# 9DOF-Razor-v22.net
KiCad netlist of a schematic drawn in EAGLE
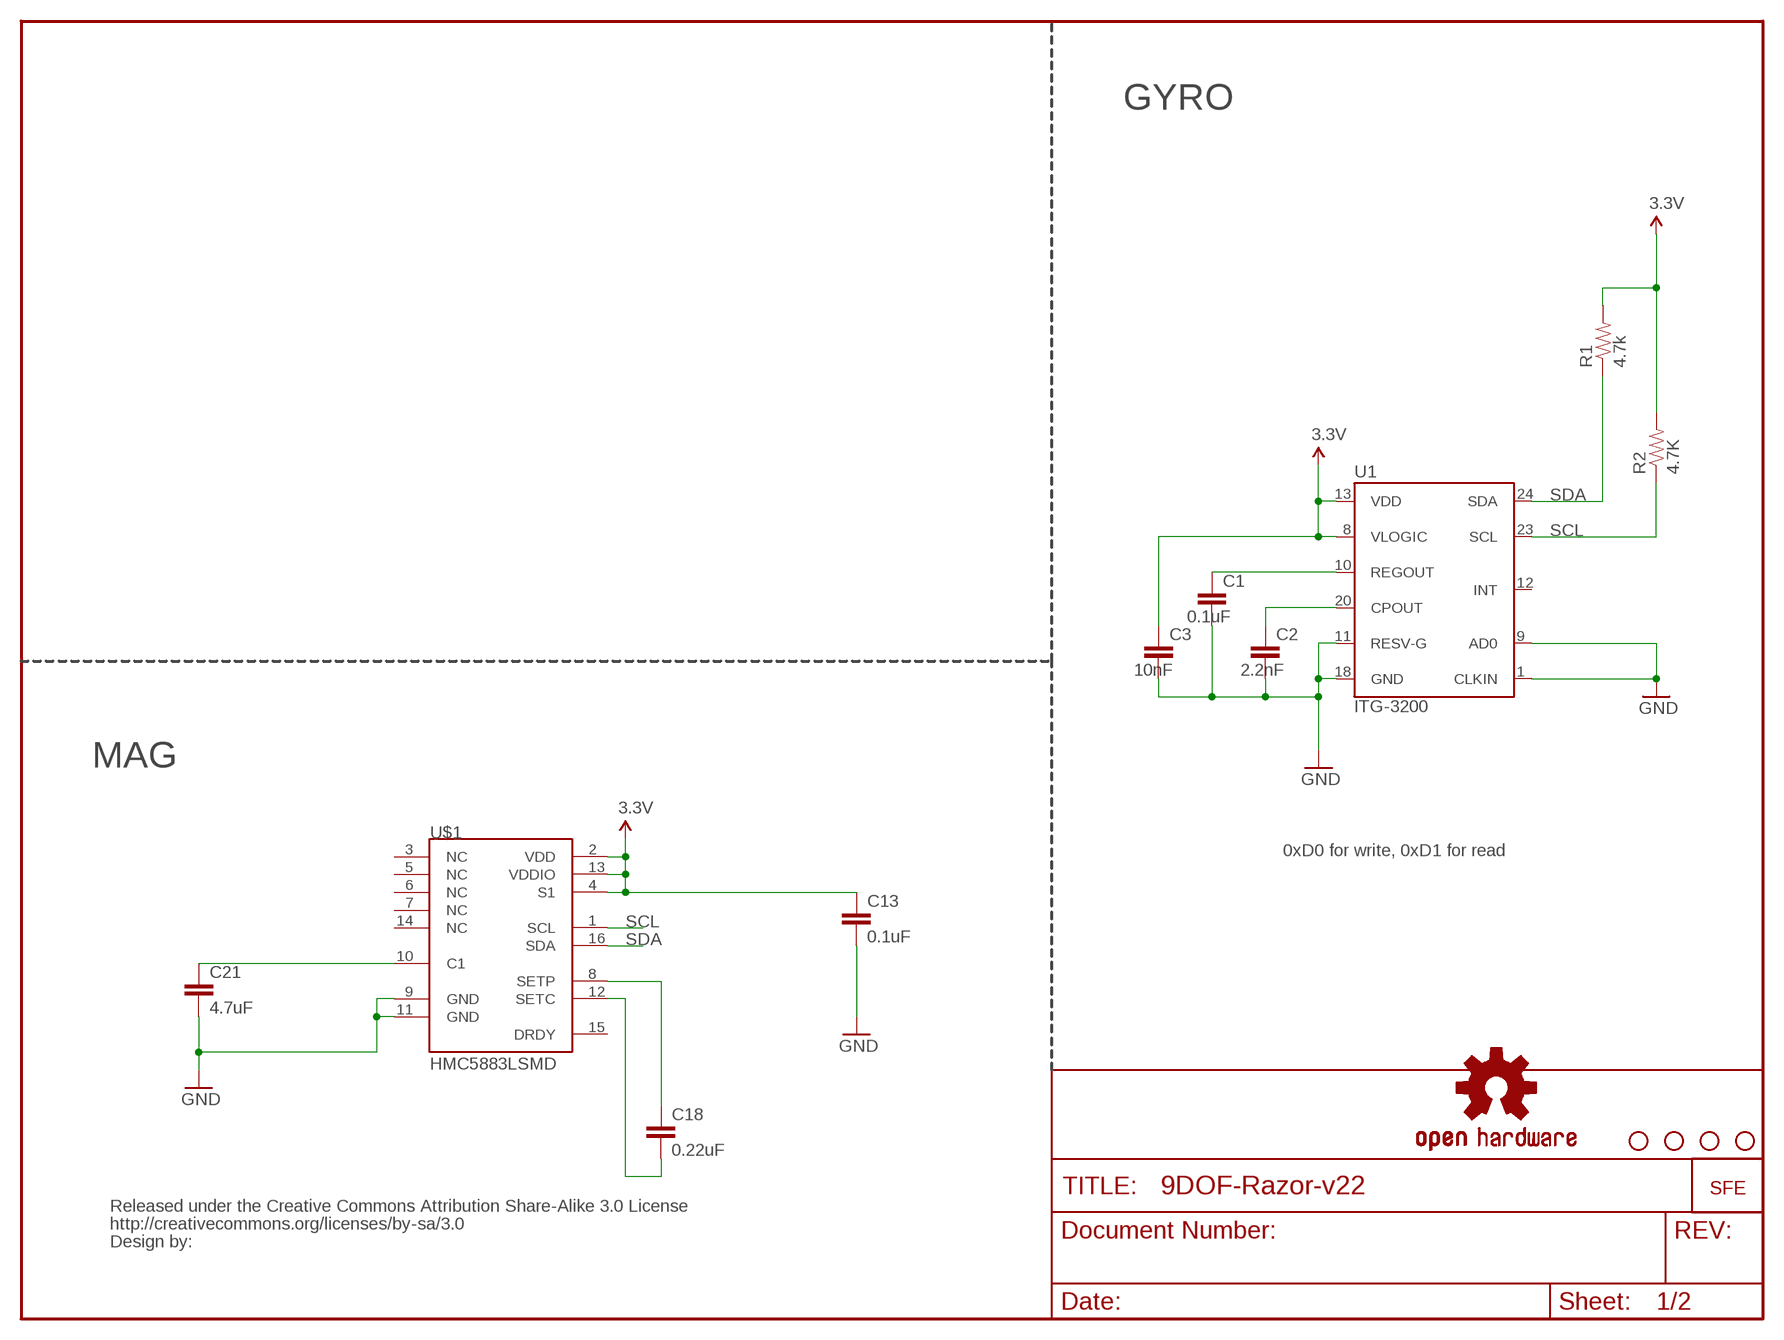
[diagram p0: schematic, sheet 1]
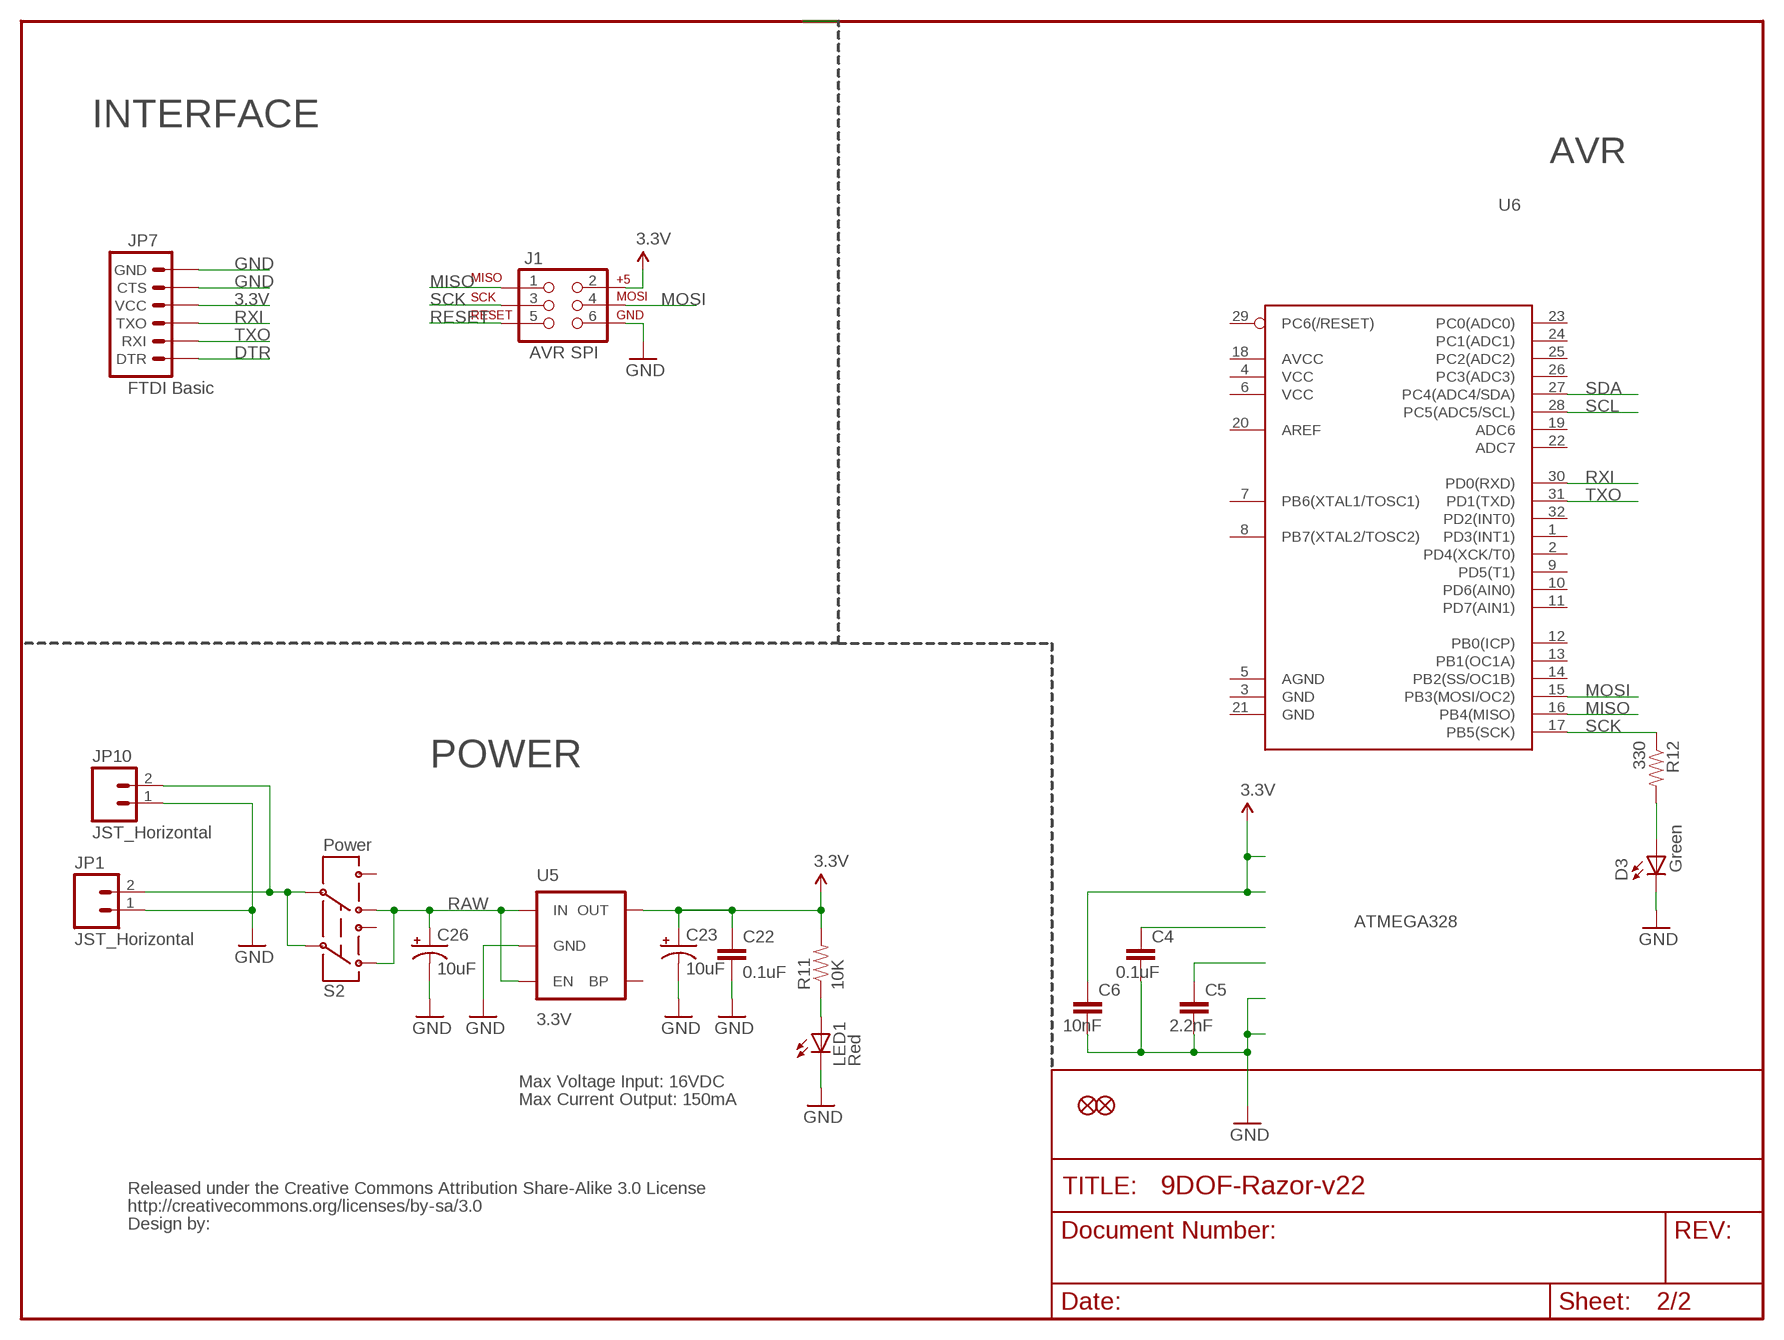
[diagram p1: schematic, sheet 2]

(export (version "E")
  (design (tool "Eeschema 10.0.6"))
  (components
    (comp (ref "C1")
      (value "0.1uF")
      (footprint "eagle-import:0402-CAP")
      (libsource (lib "eagle-import") (part "CAP0402-CAP"))
    )
    (comp (ref "C2")
      (value "2.2nF")
      (footprint "eagle-import:0402-CAP")
      (libsource (lib "eagle-import") (part "CAP0402-CAP"))
    )
    (comp (ref "C3")
      (value "10nF")
      (footprint "eagle-import:0402-CAP")
      (libsource (lib "eagle-import") (part "CAP0402-CAP"))
    )
    (comp (ref "C13")
      (value "0.1uF")
      (footprint "eagle-import:0402-CAP")
      (libsource (lib "eagle-import") (part "CAP0402-CAP"))
    )
    (comp (ref "C18")
      (value "0.22uF")
      (footprint "eagle-import:0402-CAP")
      (libsource (lib "eagle-import") (part "CAP0402-CAP"))
    )
    (comp (ref "C21")
      (value "4.7uF")
      (footprint "eagle-import:0402-CAP")
      (libsource (lib "eagle-import") (part "CAP0402-CAP"))
    )
    (comp (ref "JP2")
      (value "STAND-OFF")
      (footprint "eagle-import:STAND-OFF")
      (libsource (lib "eagle-import") (part "STAND-OFF"))
    )
    (comp (ref "JP3")
      (value "LOGO-SFENEW")
      (footprint "eagle-import:SFE-NEW-WEBLOGO")
      (libsource (lib "eagle-import") (part "LOGO-SFENEW"))
    )
    (comp (ref "JP4")
      (value "STAND-OFF")
      (footprint "eagle-import:STAND-OFF")
      (libsource (lib "eagle-import") (part "STAND-OFF"))
    )
    (comp (ref "JP5")
      (value "STAND-OFF")
      (footprint "eagle-import:STAND-OFF")
      (libsource (lib "eagle-import") (part "STAND-OFF"))
    )
    (comp (ref "JP6")
      (value "STAND-OFF")
      (footprint "eagle-import:STAND-OFF")
      (libsource (lib "eagle-import") (part "STAND-OFF"))
    )
    (comp (ref "R1")
      (value "4.7k")
      (footprint "eagle-import:0402-RES")
      (libsource (lib "eagle-import") (part "RESISTOR0402-RES"))
    )
    (comp (ref "R2")
      (value "4.7K")
      (footprint "eagle-import:0402-RES")
      (libsource (lib "eagle-import") (part "RESISTOR0402-RES"))
    )
    (comp (ref "U$1")
      (value "HMC5883LSMD")
      (footprint "eagle-import:16LPCC")
      (libsource (lib "eagle-import") (part "HMC5883LSMD"))
    )
    (comp (ref "U$2")
      (value "CREATIVE_COMMONS")
      (footprint "eagle-import:CREATIVE_COMMONS")
      (libsource (lib "eagle-import") (part "CREATIVE_COMMONS"))
    )
    (comp (ref "U$4")
      (value "OSHW-LOGOL")
      (footprint "eagle-import:OSHW-LOGO-L")
      (libsource (lib "eagle-import") (part "OSHW-LOGOL"))
    )
    (comp (ref "U1")
      (value "ITG-3200")
      (footprint "eagle-import:QFN-24")
      (libsource (lib "eagle-import") (part "ITG-3200"))
    )
    (comp (ref "C4")
      (value "0.1uF")
      (footprint "eagle-import:0402-CAP")
      (libsource (lib "eagle-import") (part "CAP0402-CAP"))
    )
    (comp (ref "C5")
      (value "2.2nF")
      (footprint "eagle-import:0402-CAP")
      (libsource (lib "eagle-import") (part "CAP0402-CAP"))
    )
    (comp (ref "C6")
      (value "10nF")
      (footprint "eagle-import:0402-CAP")
      (libsource (lib "eagle-import") (part "CAP0402-CAP"))
    )
    (comp (ref "C22")
      (value "0.1uF")
      (footprint "eagle-import:0402-CAP")
      (libsource (lib "eagle-import") (part "CAP0402-CAP"))
    )
    (comp (ref "C23")
      (value "10uF")
      (footprint "eagle-import:EIA3216")
      (libsource (lib "eagle-import") (part "CAP_POL1206"))
    )
    (comp (ref "C26")
      (value "10uF")
      (footprint "eagle-import:EIA3216")
      (libsource (lib "eagle-import") (part "CAP_POL1206"))
    )
    (comp (ref "D3")
      (value "Green")
      (footprint "eagle-import:LED-0603")
      (libsource (lib "eagle-import") (part "LED0603"))
    )
    (comp (ref "J1")
      (value "AVR_SPI_PRG_6PTH")
      (footprint "eagle-import:2X3")
      (libsource (lib "eagle-import") (part "AVR_SPI_PRG_6PTH"))
    )
    (comp (ref "JP1")
      (value "JST_Horizontal")
      (footprint "eagle-import:JST-2-SMD")
      (libsource (lib "eagle-import") (part "M02-JST-2MM-SMT"))
    )
    (comp (ref "JP7")
      (value "FTDI Basic")
      (footprint "eagle-import:1X06")
      (libsource (lib "eagle-import") (part "ARDUINO_SERIAL_PROGRAMPTH"))
    )
    (comp (ref "JP10")
      (value "JST_Horizontal")
      (footprint "eagle-import:1X02")
      (libsource (lib "eagle-import") (part "M02PTH"))
    )
    (comp (ref "JP11")
      (value "FIDUCIAL1X2.5")
      (footprint "eagle-import:FIDUCIAL-1X2.5")
      (libsource (lib "eagle-import") (part "FIDUCIAL1X2.5"))
    )
    (comp (ref "JP12")
      (value "FIDUCIAL1X2.5")
      (footprint "eagle-import:FIDUCIAL-1X2.5")
      (libsource (lib "eagle-import") (part "FIDUCIAL1X2.5"))
    )
    (comp (ref "LED1")
      (value "Red")
      (footprint "eagle-import:LED-0603")
      (libsource (lib "eagle-import") (part "LED0603"))
    )
    (comp (ref "R11")
      (value "10K")
      (footprint "eagle-import:0402-RES")
      (libsource (lib "eagle-import") (part "RESISTOR0402-RES"))
    )
    (comp (ref "R12")
      (value "330")
      (footprint "eagle-import:0402-RES")
      (libsource (lib "eagle-import") (part "RESISTOR0402-RES"))
    )
    (comp (ref "S2")
      (value "Power")
      (footprint "eagle-import:AYZ0202")
      (libsource (lib "eagle-import") (part "SWITCH-DPDTSMD"))
    )
    (comp (ref "U$3")
      (value "CREATIVE_COMMONS")
      (footprint "eagle-import:CREATIVE_COMMONS")
      (libsource (lib "eagle-import") (part "CREATIVE_COMMONS"))
    )
    (comp (ref "U5")
      (value "3.3V")
      (footprint "eagle-import:SOT23-5")
      (libsource (lib "eagle-import") (part "V_REG_LDOSMD"))
    )
    (comp (ref "U6")
      (value "ATMEGA328")
      (footprint "eagle-import:TQFP32-08")
      (libsource (lib "eagle-import") (part "ATMEGA168"))
    )
  )
  (nets
    (net (code "1") (name "3.3V") (class "Default")
      (node (ref "C13") (pin "1") (pinfunction "1_1") (pintype "passive"))
      (node (ref "C22") (pin "1") (pinfunction "1_1") (pintype "passive"))
      (node (ref "C23") (pin "A") (pinfunction "+_A") (pintype "passive"))
      (node (ref "C3") (pin "1") (pinfunction "1_1") (pintype "passive"))
      (node (ref "C6") (pin "1") (pinfunction "1_1") (pintype "passive"))
      (node (ref "J1") (pin "2") (pinfunction "2_2") (pintype "passive"))
      (node (ref "JP7") (pin "4") (pinfunction "VCC_4") (pintype "passive"))
      (node (ref "R1") (pin "2") (pinfunction "2_2") (pintype "passive"))
      (node (ref "R11") (pin "2") (pinfunction "2_2") (pintype "passive"))
      (node (ref "R2") (pin "2") (pinfunction "2_2") (pintype "passive"))
      (node (ref "U$1") (pin "13") (pinfunction "VDDIO_13") (pintype "bidirectional"))
      (node (ref "U$1") (pin "2") (pinfunction "VDD_2") (pintype "bidirectional"))
      (node (ref "U$1") (pin "4") (pinfunction "S1_4") (pintype "bidirectional"))
      (node (ref "U1") (pin "13") (pinfunction "VDD_13") (pintype "bidirectional"))
      (node (ref "U1") (pin "8") (pinfunction "VLOGIC_8") (pintype "bidirectional"))
      (node (ref "U5") (pin "5") (pinfunction "OUT_5") (pintype "passive"))
    )
    (net (code "2") (name "DTR") (class "Default")
      (node (ref "JP7") (pin "1") (pinfunction "DTR_1") (pintype "passive"))
    )
    (net (code "3") (name "GND") (class "Default")
      (node (ref "C1") (pin "2") (pinfunction "2_2") (pintype "passive"))
      (node (ref "C13") (pin "2") (pinfunction "2_2") (pintype "passive"))
      (node (ref "C2") (pin "2") (pinfunction "2_2") (pintype "passive"))
      (node (ref "C21") (pin "2") (pinfunction "2_2") (pintype "passive"))
      (node (ref "C22") (pin "2") (pinfunction "2_2") (pintype "passive"))
      (node (ref "C23") (pin "C") (pinfunction "-_C") (pintype "passive"))
      (node (ref "C26") (pin "C") (pinfunction "-_C") (pintype "passive"))
      (node (ref "C3") (pin "2") (pinfunction "2_2") (pintype "passive"))
      (node (ref "C4") (pin "2") (pinfunction "2_2") (pintype "passive"))
      (node (ref "C5") (pin "2") (pinfunction "2_2") (pintype "passive"))
      (node (ref "C6") (pin "2") (pinfunction "2_2") (pintype "passive"))
      (node (ref "D3") (pin "C") (pinfunction "C_C") (pintype "passive"))
      (node (ref "J1") (pin "6") (pinfunction "6_6") (pintype "passive"))
      (node (ref "JP1") (pin "1") (pinfunction "1_1") (pintype "passive"))
      (node (ref "JP10") (pin "1") (pinfunction "1_1") (pintype "passive"))
      (node (ref "JP7") (pin "5") (pinfunction "CTS_5") (pintype "passive"))
      (node (ref "JP7") (pin "6") (pinfunction "GND_6") (pintype "passive"))
      (node (ref "LED1") (pin "C") (pinfunction "C_C") (pintype "passive"))
      (node (ref "U$1") (pin "11") (pinfunction "GND_11") (pintype "bidirectional"))
      (node (ref "U$1") (pin "9") (pinfunction "GND_9") (pintype "bidirectional"))
      (node (ref "U1") (pin "1") (pinfunction "CLKIN_1") (pintype "bidirectional"))
      (node (ref "U1") (pin "11") (pinfunction "RESV-G_11") (pintype "bidirectional"))
      (node (ref "U1") (pin "18") (pinfunction "GND_18") (pintype "bidirectional"))
      (node (ref "U1") (pin "9") (pinfunction "AD0_9") (pintype "bidirectional"))
      (node (ref "U5") (pin "2") (pinfunction "GND_2") (pintype "input"))
    )
    (net (code "4") (name "MISO") (class "Default")
      (node (ref "J1") (pin "1") (pinfunction "1_1") (pintype "passive"))
      (node (ref "U6") (pin "16") (pinfunction "PB4(MISO)_16") (pintype "bidirectional"))
    )
    (net (code "5") (name "MOSI") (class "Default")
      (node (ref "J1") (pin "4") (pinfunction "4_4") (pintype "passive"))
      (node (ref "U6") (pin "15") (pinfunction "PB3(MOSI/OC2)_15") (pintype "bidirectional"))
    )
    (net (code "6") (name "Net-(D3-PadA)") (class "Default")
      (node (ref "D3") (pin "A") (pinfunction "A_A") (pintype "passive"))
      (node (ref "R12") (pin "2") (pinfunction "2_2") (pintype "passive"))
    )
    (net (code "7") (name "Net-(JP1-Pad2)") (class "Default")
      (node (ref "JP1") (pin "2") (pinfunction "2_2") (pintype "passive"))
      (node (ref "JP10") (pin "2") (pinfunction "2_2") (pintype "passive"))
      (node (ref "S2") (pin "2") (pinfunction "2_2") (pintype "bidirectional"))
      (node (ref "S2") (pin "5") (pinfunction "5_5") (pintype "bidirectional"))
    )
    (net (code "8") (name "Net-(LED1-PadA)") (class "Default")
      (node (ref "LED1") (pin "A") (pinfunction "A_A") (pintype "passive"))
      (node (ref "R11") (pin "1") (pinfunction "1_1") (pintype "passive"))
    )
    (net (code "9") (name "Net-(U$1-C1)") (class "Default")
      (node (ref "C21") (pin "1") (pinfunction "1_1") (pintype "passive"))
      (node (ref "U$1") (pin "10") (pinfunction "C1_10") (pintype "bidirectional"))
    )
    (net (code "10") (name "Net-(U$1-SETC)") (class "Default")
      (node (ref "C18") (pin "1") (pinfunction "1_1") (pintype "passive"))
      (node (ref "U$1") (pin "12") (pinfunction "SETC_12") (pintype "bidirectional"))
    )
    (net (code "11") (name "Net-(U$1-SETP)") (class "Default")
      (node (ref "C18") (pin "2") (pinfunction "2_2") (pintype "passive"))
      (node (ref "U$1") (pin "8") (pinfunction "SETP_8") (pintype "bidirectional"))
    )
    (net (code "12") (name "Net-(U1-CPOUT)") (class "Default")
      (node (ref "C2") (pin "1") (pinfunction "1_1") (pintype "passive"))
      (node (ref "U1") (pin "20") (pinfunction "CPOUT_20") (pintype "bidirectional"))
    )
    (net (code "13") (name "Net-(U1-REGOUT)") (class "Default")
      (node (ref "C1") (pin "1") (pinfunction "1_1") (pintype "passive"))
      (node (ref "U1") (pin "10") (pinfunction "REGOUT_10") (pintype "bidirectional"))
    )
    (net (code "14") (name "RAW") (class "Default")
      (node (ref "C26") (pin "A") (pinfunction "+_A") (pintype "passive"))
      (node (ref "S2") (pin "1") (pinfunction "1_1") (pintype "bidirectional"))
      (node (ref "S2") (pin "4") (pinfunction "4_4") (pintype "bidirectional"))
      (node (ref "U5") (pin "1") (pinfunction "IN_1") (pintype "input"))
      (node (ref "U5") (pin "3") (pinfunction "EN_3") (pintype "input"))
    )
    (net (code "15") (name "RESET") (class "Default")
      (node (ref "J1") (pin "5") (pinfunction "5_5") (pintype "passive"))
    )
    (net (code "16") (name "RXI") (class "Default")
      (node (ref "JP7") (pin "3") (pinfunction "TXO_3") (pintype "passive"))
      (node (ref "U6") (pin "30") (pinfunction "PD0(RXD)_30") (pintype "bidirectional"))
    )
    (net (code "17") (name "SCK") (class "Default")
      (node (ref "J1") (pin "3") (pinfunction "3_3") (pintype "passive"))
      (node (ref "R12") (pin "1") (pinfunction "1_1") (pintype "passive"))
      (node (ref "U6") (pin "17") (pinfunction "PB5(SCK)_17") (pintype "bidirectional"))
    )
    (net (code "18") (name "SCL") (class "Default")
      (node (ref "R2") (pin "1") (pinfunction "1_1") (pintype "passive"))
      (node (ref "U$1") (pin "1") (pinfunction "SCL_1") (pintype "bidirectional"))
      (node (ref "U1") (pin "23") (pinfunction "SCL_23") (pintype "bidirectional"))
      (node (ref "U6") (pin "28") (pinfunction "PC5(ADC5/SCL)_28") (pintype "bidirectional"))
    )
    (net (code "19") (name "SDA") (class "Default")
      (node (ref "R1") (pin "1") (pinfunction "1_1") (pintype "passive"))
      (node (ref "U$1") (pin "16") (pinfunction "SDA_16") (pintype "bidirectional"))
      (node (ref "U1") (pin "24") (pinfunction "SDA_24") (pintype "bidirectional"))
      (node (ref "U6") (pin "27") (pinfunction "PC4(ADC4/SDA)_27") (pintype "bidirectional"))
    )
    (net (code "20") (name "TXO") (class "Default")
      (node (ref "JP7") (pin "2") (pinfunction "RXI_2") (pintype "passive"))
      (node (ref "U6") (pin "31") (pinfunction "PD1(TXD)_31") (pintype "bidirectional"))
    )
    (net (code "21") (name "unconnected-(C4-Pad1)") (class "Default")
      (node (ref "C4") (pin "1") (pinfunction "1_1") (pintype "passive"))
    )
    (net (code "22") (name "unconnected-(C5-Pad1)") (class "Default")
      (node (ref "C5") (pin "1") (pinfunction "1_1") (pintype "passive"))
    )
    (net (code "23") (name "unconnected-(S2-Pad3)") (class "Default")
      (node (ref "S2") (pin "3") (pinfunction "3_3") (pintype "bidirectional"))
    )
    (net (code "24") (name "unconnected-(S2-Pad6)") (class "Default")
      (node (ref "S2") (pin "6") (pinfunction "6_6") (pintype "bidirectional"))
    )
    (net (code "25") (name "unconnected-(U$1-DRDY-Pad15)") (class "Default")
      (node (ref "U$1") (pin "15") (pinfunction "DRDY_15") (pintype "bidirectional"))
    )
    (net (code "26") (name "unconnected-(U$1-NC-Pad3)") (class "Default")
      (node (ref "U$1") (pin "3") (pinfunction "NC_3") (pintype "bidirectional"))
    )
    (net (code "27") (name "unconnected-(U$1-NC-Pad5)") (class "Default")
      (node (ref "U$1") (pin "5") (pinfunction "NC_5") (pintype "bidirectional"))
    )
    (net (code "28") (name "unconnected-(U$1-NC-Pad6)") (class "Default")
      (node (ref "U$1") (pin "6") (pinfunction "NC_6") (pintype "bidirectional"))
    )
    (net (code "29") (name "unconnected-(U$1-NC-Pad7)") (class "Default")
      (node (ref "U$1") (pin "7") (pinfunction "NC_7") (pintype "bidirectional"))
    )
    (net (code "30") (name "unconnected-(U$1-NC-Pad14)") (class "Default")
      (node (ref "U$1") (pin "14") (pinfunction "NC_14") (pintype "bidirectional"))
    )
    (net (code "31") (name "unconnected-(U1-INT-Pad12)") (class "Default")
      (node (ref "U1") (pin "12") (pinfunction "INT_12") (pintype "bidirectional"))
    )
    (net (code "32") (name "unconnected-(U5-BP-Pad4)") (class "Default")
      (node (ref "U5") (pin "4") (pinfunction "BP_4") (pintype "input"))
    )
    (net (code "33") (name "unconnected-(U6-ADC6-Pad19)") (class "Default")
      (node (ref "U6") (pin "19") (pinfunction "ADC6_19") (pintype "bidirectional"))
    )
    (net (code "34") (name "unconnected-(U6-ADC7-Pad22)") (class "Default")
      (node (ref "U6") (pin "22") (pinfunction "ADC7_22") (pintype "bidirectional"))
    )
    (net (code "35") (name "unconnected-(U6-AGND-Pad5)") (class "Default")
      (node (ref "U6") (pin "5") (pinfunction "AGND_5") (pintype "bidirectional"))
    )
    (net (code "36") (name "unconnected-(U6-AREF-Pad20)") (class "Default")
      (node (ref "U6") (pin "20") (pinfunction "AREF_20") (pintype "bidirectional"))
    )
    (net (code "37") (name "unconnected-(U6-AVCC-Pad18)") (class "Default")
      (node (ref "U6") (pin "18") (pinfunction "AVCC_18") (pintype "bidirectional"))
    )
    (net (code "38") (name "unconnected-(U6-GND-Pad3)") (class "Default")
      (node (ref "U6") (pin "3") (pinfunction "GND_3") (pintype "bidirectional"))
    )
    (net (code "39") (name "unconnected-(U6-GND-Pad21)") (class "Default")
      (node (ref "U6") (pin "21") (pinfunction "GND_21") (pintype "bidirectional"))
    )
    (net (code "40") (name "unconnected-(U6-PB0(ICP)-Pad12)") (class "Default")
      (node (ref "U6") (pin "12") (pinfunction "PB0(ICP)_12") (pintype "bidirectional"))
    )
    (net (code "41") (name "unconnected-(U6-PB1(OC1A)-Pad13)") (class "Default")
      (node (ref "U6") (pin "13") (pinfunction "PB1(OC1A)_13") (pintype "bidirectional"))
    )
    (net (code "42") (name "unconnected-(U6-PB2(SS{slash}OC1B)-Pad14)") (class "Default")
      (node (ref "U6") (pin "14") (pinfunction "PB2(SS/OC1B)_14") (pintype "bidirectional"))
    )
    (net (code "43") (name "unconnected-(U6-PB6(XTAL1{slash}TOSC1)-Pad7)") (class "Default")
      (node (ref "U6") (pin "7") (pinfunction "PB6(XTAL1/TOSC1)_7") (pintype "bidirectional"))
    )
    (net (code "44") (name "unconnected-(U6-PB7(XTAL2{slash}TOSC2)-Pad8)") (class "Default")
      (node (ref "U6") (pin "8") (pinfunction "PB7(XTAL2/TOSC2)_8") (pintype "bidirectional"))
    )
    (net (code "45") (name "unconnected-(U6-PC0(ADC0)-Pad23)") (class "Default")
      (node (ref "U6") (pin "23") (pinfunction "PC0(ADC0)_23") (pintype "bidirectional"))
    )
    (net (code "46") (name "unconnected-(U6-PC1(ADC1)-Pad24)") (class "Default")
      (node (ref "U6") (pin "24") (pinfunction "PC1(ADC1)_24") (pintype "bidirectional"))
    )
    (net (code "47") (name "unconnected-(U6-PC2(ADC2)-Pad25)") (class "Default")
      (node (ref "U6") (pin "25") (pinfunction "PC2(ADC2)_25") (pintype "bidirectional"))
    )
    (net (code "48") (name "unconnected-(U6-PC3(ADC3)-Pad26)") (class "Default")
      (node (ref "U6") (pin "26") (pinfunction "PC3(ADC3)_26") (pintype "bidirectional"))
    )
    (net (code "49") (name "unconnected-(U6-PC6({slash}RESET)-Pad29)") (class "Default")
      (node (ref "U6") (pin "29") (pinfunction "PC6(/RESET)_29") (pintype "bidirectional"))
    )
    (net (code "50") (name "unconnected-(U6-PD2(INT0)-Pad32)") (class "Default")
      (node (ref "U6") (pin "32") (pinfunction "PD2(INT0)_32") (pintype "bidirectional"))
    )
    (net (code "51") (name "unconnected-(U6-PD3(INT1)-Pad1)") (class "Default")
      (node (ref "U6") (pin "1") (pinfunction "PD3(INT1)_1") (pintype "bidirectional"))
    )
    (net (code "52") (name "unconnected-(U6-PD4(XCK{slash}T0)-Pad2)") (class "Default")
      (node (ref "U6") (pin "2") (pinfunction "PD4(XCK/T0)_2") (pintype "bidirectional"))
    )
    (net (code "53") (name "unconnected-(U6-PD5(T1)-Pad9)") (class "Default")
      (node (ref "U6") (pin "9") (pinfunction "PD5(T1)_9") (pintype "bidirectional"))
    )
    (net (code "54") (name "unconnected-(U6-PD6(AIN0)-Pad10)") (class "Default")
      (node (ref "U6") (pin "10") (pinfunction "PD6(AIN0)_10") (pintype "bidirectional"))
    )
    (net (code "55") (name "unconnected-(U6-PD7(AIN1)-Pad11)") (class "Default")
      (node (ref "U6") (pin "11") (pinfunction "PD7(AIN1)_11") (pintype "bidirectional"))
    )
    (net (code "56") (name "unconnected-(U6-VCC-Pad4)") (class "Default")
      (node (ref "U6") (pin "4") (pinfunction "VCC_4") (pintype "bidirectional"))
    )
    (net (code "57") (name "unconnected-(U6-VCC-Pad6)") (class "Default")
      (node (ref "U6") (pin "6") (pinfunction "VCC_6") (pintype "bidirectional"))
    )
  )
)
